# STM32L15x_Test.net
KiCad netlist of a schematic drawn in EAGLE
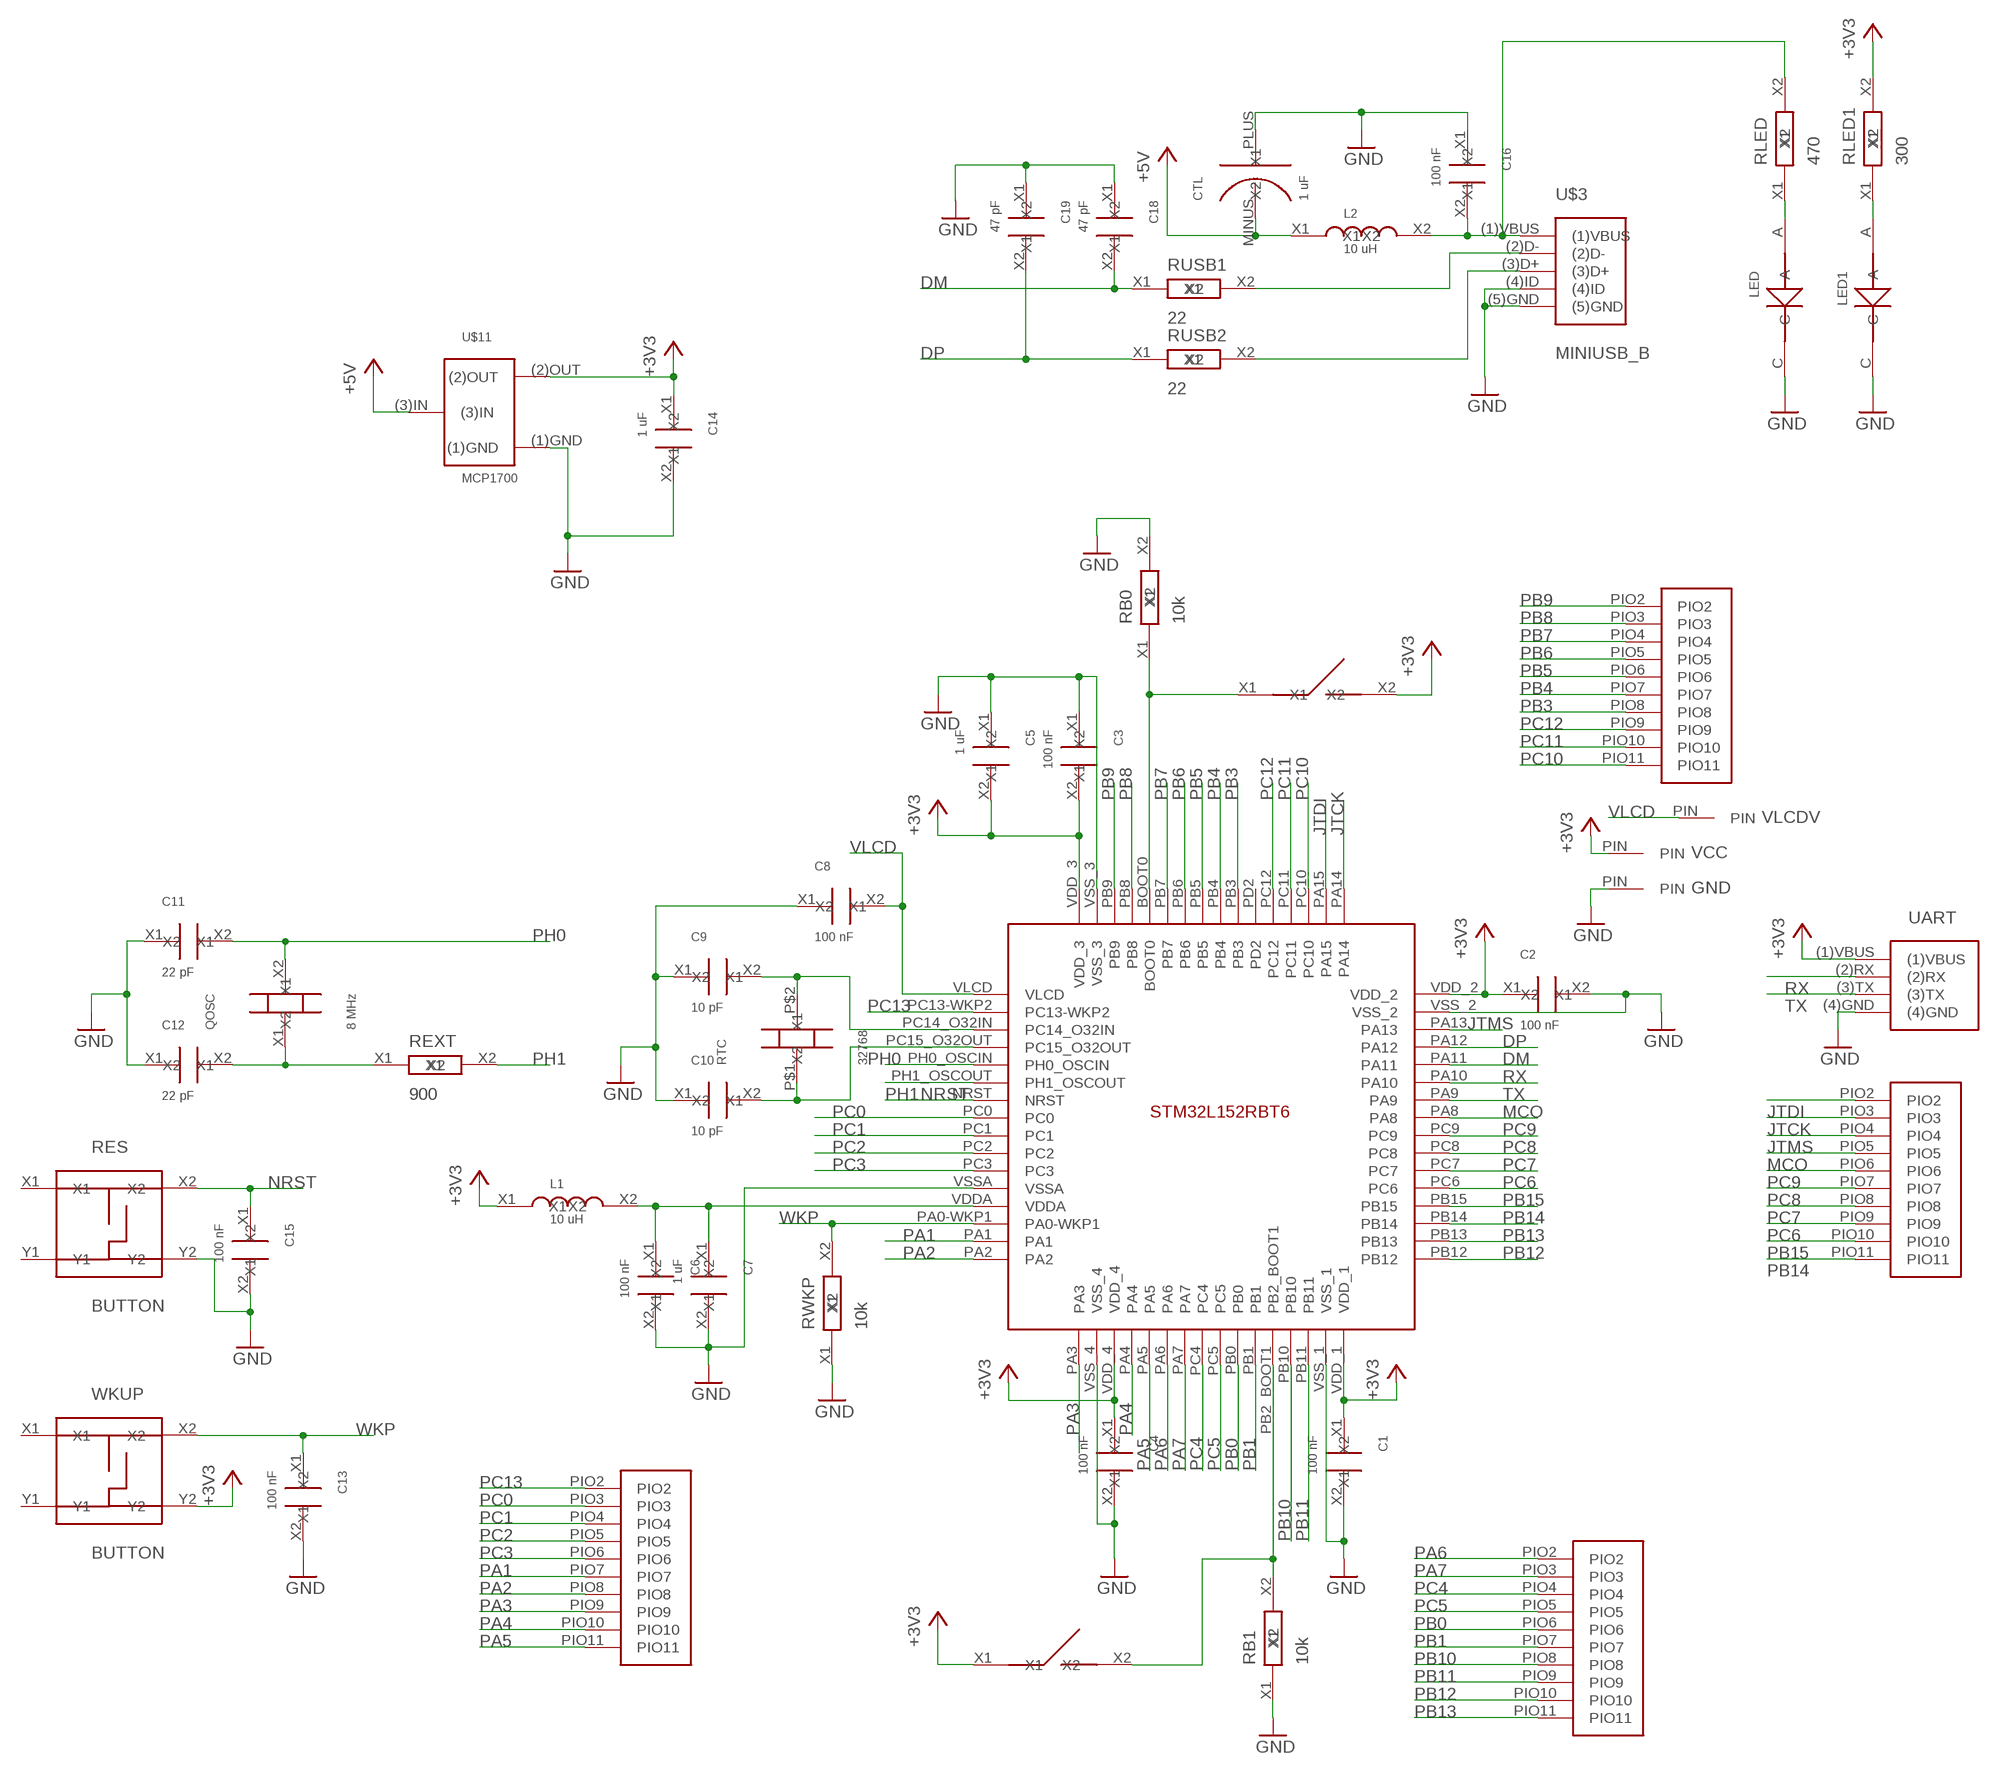
[diagram p0: schematic, sheet 1]

(export (version "E")
  (design (tool "Eeschema 10.0.6"))
  (components
    (comp (ref "C1")
      (value "100 nF")
      (footprint "eagle-import:SMD_2.1X1.25")
      (libsource (lib "eagle-import") (part "C_SMD_2.1X1.25"))
    )
    (comp (ref "C2")
      (value "100 nF")
      (footprint "eagle-import:SMD_2.1X1.25")
      (libsource (lib "eagle-import") (part "C_SMD_2.1X1.25"))
    )
    (comp (ref "C3")
      (value "100 nF")
      (footprint "eagle-import:SMD_2.1X1.25")
      (libsource (lib "eagle-import") (part "C_SMD_2.1X1.25"))
    )
    (comp (ref "C4")
      (value "100 nF")
      (footprint "eagle-import:SMD_2.1X1.25")
      (libsource (lib "eagle-import") (part "C_SMD_2.1X1.25"))
    )
    (comp (ref "C5")
      (value "1 uF")
      (footprint "eagle-import:SMD_2.1X1.25")
      (libsource (lib "eagle-import") (part "C_SMD_2.1X1.25"))
    )
    (comp (ref "C6")
      (value "100 nF")
      (footprint "eagle-import:SMD_2.1X1.25")
      (libsource (lib "eagle-import") (part "C_SMD_2.1X1.25"))
    )
    (comp (ref "C7")
      (value "1 uF")
      (footprint "eagle-import:SMD_2.1X1.25")
      (libsource (lib "eagle-import") (part "C_SMD_2.1X1.25"))
    )
    (comp (ref "C8")
      (value "100 nF")
      (footprint "eagle-import:SMD_2.1X1.25")
      (libsource (lib "eagle-import") (part "C_SMD_2.1X1.25"))
    )
    (comp (ref "C9")
      (value "10 pF")
      (footprint "eagle-import:SMD_2.1X1.25")
      (libsource (lib "eagle-import") (part "C_SMD_2.1X1.25"))
    )
    (comp (ref "C10")
      (value "10 pF")
      (footprint "eagle-import:SMD_2.1X1.25")
      (libsource (lib "eagle-import") (part "C_SMD_2.1X1.25"))
    )
    (comp (ref "C11")
      (value "22 pF")
      (footprint "eagle-import:SMD_2.1X1.25")
      (libsource (lib "eagle-import") (part "C_SMD_2.1X1.25"))
    )
    (comp (ref "C12")
      (value "22 pF")
      (footprint "eagle-import:SMD_2.1X1.25")
      (libsource (lib "eagle-import") (part "C_SMD_2.1X1.25"))
    )
    (comp (ref "C13")
      (value "100 nF")
      (footprint "eagle-import:SMD_2.1X1.25")
      (libsource (lib "eagle-import") (part "C_SMD_2.1X1.25"))
    )
    (comp (ref "C14")
      (value "1 uF")
      (footprint "eagle-import:SMD_2.1X1.25")
      (libsource (lib "eagle-import") (part "C_SMD_2.1X1.25"))
    )
    (comp (ref "C15")
      (value "100 nF")
      (footprint "eagle-import:SMD_2.1X1.25")
      (libsource (lib "eagle-import") (part "C_SMD_2.1X1.25"))
    )
    (comp (ref "C16")
      (value "100 nF")
      (footprint "eagle-import:SMD_2.1X1.25")
      (libsource (lib "eagle-import") (part "C_SMD_2.1X1.25"))
    )
    (comp (ref "C18")
      (value "47 pF")
      (footprint "eagle-import:SMD_2.1X1.25")
      (libsource (lib "eagle-import") (part "C_SMD_2.1X1.25"))
    )
    (comp (ref "C19")
      (value "47 pF")
      (footprint "eagle-import:SMD_2.1X1.25")
      (libsource (lib "eagle-import") (part "C_SMD_2.1X1.25"))
    )
    (comp (ref "CTL")
      (value "1 uF")
      (footprint "eagle-import:C_SMD_TA_A")
      (libsource (lib "eagle-import") (part "C_SMD_TA_A"))
    )
    (comp (ref "GND")
      (value "PIN")
      (footprint "eagle-import:PIN")
      (libsource (lib "eagle-import") (part "PIN"))
    )
    (comp (ref "L1")
      (value "10 uH")
      (footprint "eagle-import:SMD_2.1X1.25")
      (libsource (lib "eagle-import") (part "L_SMD_2.1X1.25"))
    )
    (comp (ref "L2")
      (value "10 uH")
      (footprint "eagle-import:SMD_2.1X1.25")
      (libsource (lib "eagle-import") (part "L_SMD_2.1X1.25"))
    )
    (comp (ref "LED")
      (value "LED0805")
      (footprint "eagle-import:SMD0805")
      (libsource (lib "eagle-import") (part "LED0805"))
    )
    (comp (ref "LED1")
      (value "LED0805")
      (footprint "eagle-import:SMD0805")
      (libsource (lib "eagle-import") (part "LED0805"))
    )
    (comp (ref "QOSC")
      (value "8 MHz")
      (footprint "eagle-import:QUARTZ_SMD")
      (libsource (lib "eagle-import") (part "QUARTZ_SMD"))
    )
    (comp (ref "RB0")
      (value "10k")
      (footprint "eagle-import:SMD_2.1X1.25")
      (libsource (lib "eagle-import") (part "R_SMD_2.1X1.25"))
    )
    (comp (ref "RB1")
      (value "10k")
      (footprint "eagle-import:SMD_2.1X1.25")
      (libsource (lib "eagle-import") (part "R_SMD_2.1X1.25"))
    )
    (comp (ref "RES")
      (value "BUTTON")
      (footprint "eagle-import:BUTTON")
      (libsource (lib "eagle-import") (part "BUTTON"))
    )
    (comp (ref "REXT")
      (value "900")
      (footprint "eagle-import:SMD_2.1X1.25")
      (libsource (lib "eagle-import") (part "R_SMD_2.1X1.25"))
    )
    (comp (ref "RLED")
      (value "470")
      (footprint "eagle-import:SMD_2.1X1.25")
      (libsource (lib "eagle-import") (part "R_SMD_2.1X1.25"))
    )
    (comp (ref "RLED1")
      (value "300")
      (footprint "eagle-import:SMD_2.1X1.25")
      (libsource (lib "eagle-import") (part "R_SMD_2.1X1.25"))
    )
    (comp (ref "RTC")
      (value "32768")
      (footprint "eagle-import:QUARTZ_CYL")
      (libsource (lib "eagle-import") (part "QUARTZ_CYL"))
    )
    (comp (ref "RUSB1")
      (value "22")
      (footprint "eagle-import:SMD_2.1X1.25")
      (libsource (lib "eagle-import") (part "R_SMD_2.1X1.25"))
    )
    (comp (ref "RUSB2")
      (value "22")
      (footprint "eagle-import:SMD_2.1X1.25")
      (libsource (lib "eagle-import") (part "R_SMD_2.1X1.25"))
    )
    (comp (ref "RWKP")
      (value "10k")
      (footprint "eagle-import:SMD_2.1X1.25")
      (libsource (lib "eagle-import") (part "R_SMD_2.1X1.25"))
    )
    (comp (ref "U$1")
      (value "STM32L15XRBT6")
      (footprint "eagle-import:STM32L152RBT6")
      (libsource (lib "eagle-import") (part "STM32L15XRBT6"))
    )
    (comp (ref "U$2")
      (value "PIO_10")
      (footprint "eagle-import:PIO_10")
      (libsource (lib "eagle-import") (part "PIO_10"))
    )
    (comp (ref "U$3")
      (value "MINIUSB_B")
      (footprint "eagle-import:MINIUSB_B")
      (libsource (lib "eagle-import") (part "MINIUSB_B"))
    )
    (comp (ref "U$5")
      (value "PIO_10")
      (footprint "eagle-import:PIO_10")
      (libsource (lib "eagle-import") (part "PIO_10"))
    )
    (comp (ref "U$6")
      (value "PIO_10")
      (footprint "eagle-import:PIO_10")
      (libsource (lib "eagle-import") (part "PIO_10"))
    )
    (comp (ref "U$7")
      (value "PIO_10")
      (footprint "eagle-import:PIO_10")
      (libsource (lib "eagle-import") (part "PIO_10"))
    )
    (comp (ref "U$8")
      (value "DIP_1")
      (footprint "eagle-import:DIP_1")
      (libsource (lib "eagle-import") (part "DIP_1"))
    )
    (comp (ref "U$9")
      (value "DIP_1")
      (footprint "eagle-import:DIP_1")
      (libsource (lib "eagle-import") (part "DIP_1"))
    )
    (comp (ref "U$11")
      (value "MCP1700")
      (footprint "eagle-import:MCP1700")
      (libsource (lib "eagle-import") (part "MCP1700"))
    )
    (comp (ref "UART")
      (value "USART")
      (footprint "eagle-import:USART")
      (libsource (lib "eagle-import") (part "USART"))
    )
    (comp (ref "VCC")
      (value "PIN")
      (footprint "eagle-import:PIN")
      (libsource (lib "eagle-import") (part "PIN"))
    )
    (comp (ref "VLCDV")
      (value "PIN")
      (footprint "eagle-import:PIN")
      (libsource (lib "eagle-import") (part "PIN"))
    )
    (comp (ref "WKUP")
      (value "BUTTON")
      (footprint "eagle-import:BUTTON")
      (libsource (lib "eagle-import") (part "BUTTON"))
    )
  )
  (nets
    (net (code "1") (name "+3V3") (class "Default")
      (node (ref "C1") (pin "X1") (pinfunction "X1_X1") (pintype "bidirectional"))
      (node (ref "C14") (pin "X1") (pinfunction "X1_X1") (pintype "bidirectional"))
      (node (ref "C2") (pin "X1") (pinfunction "X1_X1") (pintype "bidirectional"))
      (node (ref "C3") (pin "X2") (pinfunction "X2_X2") (pintype "bidirectional"))
      (node (ref "C4") (pin "X1") (pinfunction "X1_X1") (pintype "bidirectional"))
      (node (ref "C5") (pin "X2") (pinfunction "X2_X2") (pintype "bidirectional"))
      (node (ref "L1") (pin "X1") (pinfunction "X1_X1") (pintype "bidirectional"))
      (node (ref "RLED1") (pin "X2") (pinfunction "X2_X2") (pintype "bidirectional"))
      (node (ref "U$1") (pin "VDD_1") (pinfunction "VDD_1_VDD_1") (pintype "bidirectional"))
      (node (ref "U$1") (pin "VDD_2") (pinfunction "VDD_2_VDD_2") (pintype "bidirectional"))
      (node (ref "U$1") (pin "VDD_3") (pinfunction "VDD_3_VDD_3") (pintype "bidirectional"))
      (node (ref "U$1") (pin "VDD_4") (pinfunction "VDD_4_VDD_4") (pintype "bidirectional"))
      (node (ref "U$11") (pin "(2)OUT") (pinfunction "(2)OUT_(2)OUT") (pintype "bidirectional"))
      (node (ref "U$8") (pin "X2") (pinfunction "X2_X2") (pintype "bidirectional"))
      (node (ref "U$9") (pin "X1") (pinfunction "X1_X1") (pintype "bidirectional"))
      (node (ref "UART") (pin "(1)VBUS") (pinfunction "(1)VBUS_(1)VBUS") (pintype "bidirectional"))
      (node (ref "VCC") (pin "PIN") (pinfunction "PIN_PIN") (pintype "bidirectional"))
      (node (ref "WKUP") (pin "Y2") (pinfunction "Y2_Y2") (pintype "bidirectional"))
    )
    (net (code "2") (name "+5V") (class "Default")
      (node (ref "CTL") (pin "MINUS") (pinfunction "X1_MINUS") (pintype "bidirectional"))
      (node (ref "L2") (pin "X1") (pinfunction "X1_X1") (pintype "bidirectional"))
      (node (ref "U$11") (pin "(3)IN") (pinfunction "(3)IN_(3)IN") (pintype "bidirectional"))
    )
    (net (code "3") (name "/DM") (class "Default")
      (node (ref "C18") (pin "X2") (pinfunction "X2_X2") (pintype "bidirectional"))
      (node (ref "RUSB1") (pin "X1") (pinfunction "X1_X1") (pintype "bidirectional"))
      (node (ref "U$1") (pin "PA11") (pinfunction "PA11_PA11") (pintype "bidirectional"))
    )
    (net (code "4") (name "/DP") (class "Default")
      (node (ref "C19") (pin "X2") (pinfunction "X2_X2") (pintype "bidirectional"))
      (node (ref "RUSB2") (pin "X1") (pinfunction "X1_X1") (pintype "bidirectional"))
      (node (ref "U$1") (pin "PA12") (pinfunction "PA12_PA12") (pintype "bidirectional"))
    )
    (net (code "5") (name "/JTCK") (class "Default")
      (node (ref "U$1") (pin "PA14") (pinfunction "PA14_PA14") (pintype "bidirectional"))
      (node (ref "U$6") (pin "PIO3") (pinfunction "PIO3_PIO3") (pintype "bidirectional"))
    )
    (net (code "6") (name "/JTDI") (class "Default")
      (node (ref "U$1") (pin "PA15") (pinfunction "PA15_PA15") (pintype "bidirectional"))
      (node (ref "U$6") (pin "PIO2") (pinfunction "PIO2_PIO2") (pintype "bidirectional"))
    )
    (net (code "7") (name "/JTMS") (class "Default")
      (node (ref "U$1") (pin "PA13") (pinfunction "PA13_PA13") (pintype "bidirectional"))
      (node (ref "U$6") (pin "PIO4") (pinfunction "PIO4_PIO4") (pintype "bidirectional"))
    )
    (net (code "8") (name "/MCO") (class "Default")
      (node (ref "U$1") (pin "PA8") (pinfunction "PA8_PA8") (pintype "bidirectional"))
      (node (ref "U$6") (pin "PIO5") (pinfunction "PIO5_PIO5") (pintype "bidirectional"))
    )
    (net (code "9") (name "/NRST") (class "Default")
      (node (ref "C15") (pin "X1") (pinfunction "X1_X1") (pintype "bidirectional"))
      (node (ref "RES") (pin "X2") (pinfunction "X2_X2") (pintype "bidirectional"))
      (node (ref "U$1") (pin "NRST") (pinfunction "NRST_NRST") (pintype "bidirectional"))
    )
    (net (code "10") (name "/PA1") (class "Default")
      (node (ref "U$1") (pin "PA1") (pinfunction "PA1_PA1") (pintype "bidirectional"))
      (node (ref "U$2") (pin "PIO7") (pinfunction "PIO7_PIO7") (pintype "bidirectional"))
    )
    (net (code "11") (name "/PA2") (class "Default")
      (node (ref "U$1") (pin "PA2") (pinfunction "PA2_PA2") (pintype "bidirectional"))
      (node (ref "U$2") (pin "PIO8") (pinfunction "PIO8_PIO8") (pintype "bidirectional"))
    )
    (net (code "12") (name "/PA3") (class "Default")
      (node (ref "U$1") (pin "PA3") (pinfunction "PA3_PA3") (pintype "bidirectional"))
      (node (ref "U$2") (pin "PIO9") (pinfunction "PIO9_PIO9") (pintype "bidirectional"))
    )
    (net (code "13") (name "/PA4") (class "Default")
      (node (ref "U$1") (pin "PA4") (pinfunction "PA4_PA4") (pintype "bidirectional"))
      (node (ref "U$2") (pin "PIO10") (pinfunction "PIO10_PIO10") (pintype "bidirectional"))
    )
    (net (code "14") (name "/PA5") (class "Default")
      (node (ref "U$1") (pin "PA5") (pinfunction "PA5_PA5") (pintype "bidirectional"))
      (node (ref "U$2") (pin "PIO11") (pinfunction "PIO11_PIO11") (pintype "bidirectional"))
    )
    (net (code "15") (name "/PA6") (class "Default")
      (node (ref "U$1") (pin "PA6") (pinfunction "PA6_PA6") (pintype "bidirectional"))
      (node (ref "U$5") (pin "PIO2") (pinfunction "PIO2_PIO2") (pintype "bidirectional"))
    )
    (net (code "16") (name "/PA7") (class "Default")
      (node (ref "U$1") (pin "PA7") (pinfunction "PA7_PA7") (pintype "bidirectional"))
      (node (ref "U$5") (pin "PIO3") (pinfunction "PIO3_PIO3") (pintype "bidirectional"))
    )
    (net (code "17") (name "/PB0") (class "Default")
      (node (ref "U$1") (pin "PB0") (pinfunction "PB0_PB0") (pintype "bidirectional"))
      (node (ref "U$5") (pin "PIO6") (pinfunction "PIO6_PIO6") (pintype "bidirectional"))
    )
    (net (code "18") (name "/PB1") (class "Default")
      (node (ref "U$1") (pin "PB1") (pinfunction "PB1_PB1") (pintype "bidirectional"))
      (node (ref "U$5") (pin "PIO7") (pinfunction "PIO7_PIO7") (pintype "bidirectional"))
    )
    (net (code "19") (name "/PB3") (class "Default")
      (node (ref "U$1") (pin "PB3") (pinfunction "PB3_PB3") (pintype "bidirectional"))
      (node (ref "U$7") (pin "PIO8") (pinfunction "PIO8_PIO8") (pintype "bidirectional"))
    )
    (net (code "20") (name "/PB4") (class "Default")
      (node (ref "U$1") (pin "PB4") (pinfunction "PB4_PB4") (pintype "bidirectional"))
      (node (ref "U$7") (pin "PIO7") (pinfunction "PIO7_PIO7") (pintype "bidirectional"))
    )
    (net (code "21") (name "/PB5") (class "Default")
      (node (ref "U$1") (pin "PB5") (pinfunction "PB5_PB5") (pintype "bidirectional"))
      (node (ref "U$7") (pin "PIO6") (pinfunction "PIO6_PIO6") (pintype "bidirectional"))
    )
    (net (code "22") (name "/PB6") (class "Default")
      (node (ref "U$1") (pin "PB6") (pinfunction "PB6_PB6") (pintype "bidirectional"))
      (node (ref "U$7") (pin "PIO5") (pinfunction "PIO5_PIO5") (pintype "bidirectional"))
    )
    (net (code "23") (name "/PB7") (class "Default")
      (node (ref "U$1") (pin "PB7") (pinfunction "PB7_PB7") (pintype "bidirectional"))
      (node (ref "U$7") (pin "PIO4") (pinfunction "PIO4_PIO4") (pintype "bidirectional"))
    )
    (net (code "24") (name "/PB8") (class "Default")
      (node (ref "U$1") (pin "PB8") (pinfunction "PB8_PB8") (pintype "bidirectional"))
      (node (ref "U$7") (pin "PIO3") (pinfunction "PIO3_PIO3") (pintype "bidirectional"))
    )
    (net (code "25") (name "/PB9") (class "Default")
      (node (ref "U$1") (pin "PB9") (pinfunction "PB9_PB9") (pintype "bidirectional"))
      (node (ref "U$7") (pin "PIO2") (pinfunction "PIO2_PIO2") (pintype "bidirectional"))
    )
    (net (code "26") (name "/PB10") (class "Default")
      (node (ref "U$1") (pin "PB10") (pinfunction "PB10_PB10") (pintype "bidirectional"))
      (node (ref "U$5") (pin "PIO8") (pinfunction "PIO8_PIO8") (pintype "bidirectional"))
    )
    (net (code "27") (name "/PB11") (class "Default")
      (node (ref "U$1") (pin "PB11") (pinfunction "PB11_PB11") (pintype "bidirectional"))
      (node (ref "U$5") (pin "PIO9") (pinfunction "PIO9_PIO9") (pintype "bidirectional"))
    )
    (net (code "28") (name "/PB12") (class "Default")
      (node (ref "U$1") (pin "PB12") (pinfunction "PB12_PB12") (pintype "bidirectional"))
      (node (ref "U$5") (pin "PIO10") (pinfunction "PIO10_PIO10") (pintype "bidirectional"))
    )
    (net (code "29") (name "/PB13") (class "Default")
      (node (ref "U$1") (pin "PB13") (pinfunction "PB13_PB13") (pintype "bidirectional"))
      (node (ref "U$5") (pin "PIO11") (pinfunction "PIO11_PIO11") (pintype "bidirectional"))
    )
    (net (code "30") (name "/PB14") (class "Default")
      (node (ref "U$1") (pin "PB14") (pinfunction "PB14_PB14") (pintype "bidirectional"))
      (node (ref "U$6") (pin "PIO11") (pinfunction "PIO11_PIO11") (pintype "bidirectional"))
    )
    (net (code "31") (name "/PB15") (class "Default")
      (node (ref "U$1") (pin "PB15") (pinfunction "PB15_PB15") (pintype "bidirectional"))
      (node (ref "U$6") (pin "PIO10") (pinfunction "PIO10_PIO10") (pintype "bidirectional"))
    )
    (net (code "32") (name "/PC0") (class "Default")
      (node (ref "U$1") (pin "PC0") (pinfunction "PC0_PC0") (pintype "bidirectional"))
      (node (ref "U$2") (pin "PIO3") (pinfunction "PIO3_PIO3") (pintype "bidirectional"))
    )
    (net (code "33") (name "/PC1") (class "Default")
      (node (ref "U$1") (pin "PC1") (pinfunction "PC1_PC1") (pintype "bidirectional"))
      (node (ref "U$2") (pin "PIO4") (pinfunction "PIO4_PIO4") (pintype "bidirectional"))
    )
    (net (code "34") (name "/PC2") (class "Default")
      (node (ref "U$1") (pin "PC2") (pinfunction "PC2_PC2") (pintype "bidirectional"))
      (node (ref "U$2") (pin "PIO5") (pinfunction "PIO5_PIO5") (pintype "bidirectional"))
    )
    (net (code "35") (name "/PC3") (class "Default")
      (node (ref "U$1") (pin "PC3") (pinfunction "PC3_PC3") (pintype "bidirectional"))
      (node (ref "U$2") (pin "PIO6") (pinfunction "PIO6_PIO6") (pintype "bidirectional"))
    )
    (net (code "36") (name "/PC4") (class "Default")
      (node (ref "U$1") (pin "PC4") (pinfunction "PC4_PC4") (pintype "bidirectional"))
      (node (ref "U$5") (pin "PIO4") (pinfunction "PIO4_PIO4") (pintype "bidirectional"))
    )
    (net (code "37") (name "/PC5") (class "Default")
      (node (ref "U$1") (pin "PC5") (pinfunction "PC5_PC5") (pintype "bidirectional"))
      (node (ref "U$5") (pin "PIO5") (pinfunction "PIO5_PIO5") (pintype "bidirectional"))
    )
    (net (code "38") (name "/PC6") (class "Default")
      (node (ref "U$1") (pin "PC6") (pinfunction "PC6_PC6") (pintype "bidirectional"))
      (node (ref "U$6") (pin "PIO9") (pinfunction "PIO9_PIO9") (pintype "bidirectional"))
    )
    (net (code "39") (name "/PC7") (class "Default")
      (node (ref "U$1") (pin "PC7") (pinfunction "PC7_PC7") (pintype "bidirectional"))
      (node (ref "U$6") (pin "PIO8") (pinfunction "PIO8_PIO8") (pintype "bidirectional"))
    )
    (net (code "40") (name "/PC8") (class "Default")
      (node (ref "U$1") (pin "PC8") (pinfunction "PC8_PC8") (pintype "bidirectional"))
      (node (ref "U$6") (pin "PIO7") (pinfunction "PIO7_PIO7") (pintype "bidirectional"))
    )
    (net (code "41") (name "/PC9") (class "Default")
      (node (ref "U$1") (pin "PC9") (pinfunction "PC9_PC9") (pintype "bidirectional"))
      (node (ref "U$6") (pin "PIO6") (pinfunction "PIO6_PIO6") (pintype "bidirectional"))
    )
    (net (code "42") (name "/PC10") (class "Default")
      (node (ref "U$1") (pin "PC10") (pinfunction "PC10_PC10") (pintype "bidirectional"))
      (node (ref "U$7") (pin "PIO11") (pinfunction "PIO11_PIO11") (pintype "bidirectional"))
    )
    (net (code "43") (name "/PC11") (class "Default")
      (node (ref "U$1") (pin "PC11") (pinfunction "PC11_PC11") (pintype "bidirectional"))
      (node (ref "U$7") (pin "PIO10") (pinfunction "PIO10_PIO10") (pintype "bidirectional"))
    )
    (net (code "44") (name "/PC12") (class "Default")
      (node (ref "U$1") (pin "PC12") (pinfunction "PC12_PC12") (pintype "bidirectional"))
      (node (ref "U$7") (pin "PIO9") (pinfunction "PIO9_PIO9") (pintype "bidirectional"))
    )
    (net (code "45") (name "/PC13") (class "Default")
      (node (ref "U$1") (pin "PC13-WKP2") (pinfunction "PC13-WKP2_PC13-WKP2") (pintype "bidirectional"))
      (node (ref "U$2") (pin "PIO2") (pinfunction "PIO2_PIO2") (pintype "bidirectional"))
    )
    (net (code "46") (name "/PH0") (class "Default")
      (node (ref "C11") (pin "X2") (pinfunction "X2_X2") (pintype "bidirectional"))
      (node (ref "QOSC") (pin "X2") (pinfunction "X2_X2") (pintype "bidirectional"))
      (node (ref "U$1") (pin "PH0_OSCIN") (pinfunction "PH0_OSCIN_PH0_OSCIN") (pintype "bidirectional"))
    )
    (net (code "47") (name "/PH1") (class "Default")
      (node (ref "REXT") (pin "X2") (pinfunction "X2_X2") (pintype "bidirectional"))
      (node (ref "U$1") (pin "PH1_OSCOUT") (pinfunction "PH1_OSCOUT_PH1_OSCOUT") (pintype "bidirectional"))
    )
    (net (code "48") (name "/RX") (class "Default")
      (node (ref "U$1") (pin "PA10") (pinfunction "PA10_PA10") (pintype "bidirectional"))
      (node (ref "UART") (pin "(2)RX") (pinfunction "(2)RX_(2)RX") (pintype "bidirectional"))
    )
    (net (code "49") (name "/TX") (class "Default")
      (node (ref "U$1") (pin "PA9") (pinfunction "PA9_PA9") (pintype "bidirectional"))
      (node (ref "UART") (pin "(3)TX") (pinfunction "(3)TX_(3)TX") (pintype "bidirectional"))
    )
    (net (code "50") (name "/VLCD") (class "Default")
      (node (ref "C8") (pin "X2") (pinfunction "X2_X2") (pintype "bidirectional"))
      (node (ref "U$1") (pin "VLCD") (pinfunction "VLCD_VLCD") (pintype "bidirectional"))
      (node (ref "VLCDV") (pin "PIN") (pinfunction "PIN_PIN") (pintype "bidirectional"))
    )
    (net (code "51") (name "/WKP") (class "Default")
      (node (ref "C13") (pin "X1") (pinfunction "X1_X1") (pintype "bidirectional"))
      (node (ref "RWKP") (pin "X2") (pinfunction "X2_X2") (pintype "bidirectional"))
      (node (ref "U$1") (pin "PA0-WKP1") (pinfunction "PA0-WKP1_PA0-WKP1") (pintype "bidirectional"))
      (node (ref "WKUP") (pin "X2") (pinfunction "X2_X2") (pintype "bidirectional"))
    )
    (net (code "52") (name "GND") (class "Default")
      (node (ref "C1") (pin "X2") (pinfunction "X2_X2") (pintype "bidirectional"))
      (node (ref "C10") (pin "X1") (pinfunction "X1_X1") (pintype "bidirectional"))
      (node (ref "C11") (pin "X1") (pinfunction "X1_X1") (pintype "bidirectional"))
      (node (ref "C12") (pin "X1") (pinfunction "X1_X1") (pintype "bidirectional"))
      (node (ref "C13") (pin "X2") (pinfunction "X2_X2") (pintype "bidirectional"))
      (node (ref "C14") (pin "X2") (pinfunction "X2_X2") (pintype "bidirectional"))
      (node (ref "C15") (pin "X2") (pinfunction "X2_X2") (pintype "bidirectional"))
      (node (ref "C16") (pin "X1") (pinfunction "X1_X1") (pintype "bidirectional"))
      (node (ref "C18") (pin "X1") (pinfunction "X1_X1") (pintype "bidirectional"))
      (node (ref "C19") (pin "X1") (pinfunction "X1_X1") (pintype "bidirectional"))
      (node (ref "C2") (pin "X2") (pinfunction "X2_X2") (pintype "bidirectional"))
      (node (ref "C3") (pin "X1") (pinfunction "X1_X1") (pintype "bidirectional"))
      (node (ref "C4") (pin "X2") (pinfunction "X2_X2") (pintype "bidirectional"))
      (node (ref "C5") (pin "X1") (pinfunction "X1_X1") (pintype "bidirectional"))
      (node (ref "C6") (pin "X2") (pinfunction "X2_X2") (pintype "bidirectional"))
      (node (ref "C7") (pin "X2") (pinfunction "X2_X2") (pintype "bidirectional"))
      (node (ref "C8") (pin "X1") (pinfunction "X1_X1") (pintype "bidirectional"))
      (node (ref "C9") (pin "X1") (pinfunction "X1_X1") (pintype "bidirectional"))
      (node (ref "CTL") (pin "PLUS") (pinfunction "X2_PLUS") (pintype "bidirectional"))
      (node (ref "GND") (pin "PIN") (pinfunction "PIN_PIN") (pintype "bidirectional"))
      (node (ref "LED") (pin "C") (pinfunction "C_C") (pintype "bidirectional"))
      (node (ref "LED1") (pin "C") (pinfunction "C_C") (pintype "bidirectional"))
      (node (ref "RB0") (pin "X2") (pinfunction "X2_X2") (pintype "bidirectional"))
      (node (ref "RB1") (pin "X1") (pinfunction "X1_X1") (pintype "bidirectional"))
      (node (ref "RES") (pin "Y2") (pinfunction "Y2_Y2") (pintype "bidirectional"))
      (node (ref "RWKP") (pin "X1") (pinfunction "X1_X1") (pintype "bidirectional"))
      (node (ref "U$1") (pin "VSSA") (pinfunction "VSSA_VSSA") (pintype "bidirectional"))
      (node (ref "U$1") (pin "VSS_1") (pinfunction "VSS_1_VSS_1") (pintype "bidirectional"))
      (node (ref "U$1") (pin "VSS_2") (pinfunction "VSS_2_VSS_2") (pintype "bidirectional"))
      (node (ref "U$1") (pin "VSS_3") (pinfunction "VSS_3_VSS_3") (pintype "bidirectional"))
      (node (ref "U$1") (pin "VSS_4") (pinfunction "VSS_4_VSS_4") (pintype "bidirectional"))
      (node (ref "U$11") (pin "(1)GND") (pinfunction "(1)GND_(1)GND") (pintype "bidirectional"))
      (node (ref "U$3") (pin "(4)ID") (pinfunction "(4)ID_(4)ID") (pintype "bidirectional"))
      (node (ref "U$3") (pin "(5)GND") (pinfunction "(5)GND_(5)GND") (pintype "bidirectional"))
      (node (ref "UART") (pin "(4)GND") (pinfunction "(4)GND_(4)GND") (pintype "bidirectional"))
    )
    (net (code "53") (name "Net-(C6-PadX1)") (class "Default")
      (node (ref "C6") (pin "X1") (pinfunction "X1_X1") (pintype "bidirectional"))
      (node (ref "C7") (pin "X1") (pinfunction "X1_X1") (pintype "bidirectional"))
      (node (ref "L1") (pin "X2") (pinfunction "X2_X2") (pintype "bidirectional"))
      (node (ref "U$1") (pin "VDDA") (pinfunction "VDDA_VDDA") (pintype "bidirectional"))
    )
    (net (code "54") (name "Net-(C12-PadX2)") (class "Default")
      (node (ref "C12") (pin "X2") (pinfunction "X2_X2") (pintype "bidirectional"))
      (node (ref "QOSC") (pin "X1") (pinfunction "X1_X1") (pintype "bidirectional"))
      (node (ref "REXT") (pin "X1") (pinfunction "X1_X1") (pintype "bidirectional"))
    )
    (net (code "55") (name "Net-(C16-PadX2)") (class "Default")
      (node (ref "C16") (pin "X2") (pinfunction "X2_X2") (pintype "bidirectional"))
      (node (ref "L2") (pin "X2") (pinfunction "X2_X2") (pintype "bidirectional"))
      (node (ref "RLED") (pin "X2") (pinfunction "X2_X2") (pintype "bidirectional"))
      (node (ref "U$3") (pin "(1)VBUS") (pinfunction "(1)VBUS_(1)VBUS") (pintype "bidirectional"))
    )
    (net (code "56") (name "Net-(LED-PadA)") (class "Default")
      (node (ref "LED") (pin "A") (pinfunction "A_A") (pintype "bidirectional"))
      (node (ref "RLED") (pin "X1") (pinfunction "X1_X1") (pintype "bidirectional"))
    )
    (net (code "57") (name "Net-(LED1-PadA)") (class "Default")
      (node (ref "LED1") (pin "A") (pinfunction "A_A") (pintype "bidirectional"))
      (node (ref "RLED1") (pin "X1") (pinfunction "X1_X1") (pintype "bidirectional"))
    )
    (net (code "58") (name "Net-(RB0-PadX1)") (class "Default")
      (node (ref "RB0") (pin "X1") (pinfunction "X1_X1") (pintype "bidirectional"))
      (node (ref "U$1") (pin "BOOT0") (pinfunction "BOOT0_BOOT0") (pintype "bidirectional"))
      (node (ref "U$8") (pin "X1") (pinfunction "X1_X1") (pintype "bidirectional"))
    )
    (net (code "59") (name "Net-(RB1-PadX2)") (class "Default")
      (node (ref "RB1") (pin "X2") (pinfunction "X2_X2") (pintype "bidirectional"))
      (node (ref "U$1") (pin "PB2_BOOT1") (pinfunction "PB2_BOOT1_PB2_BOOT1") (pintype "bidirectional"))
      (node (ref "U$9") (pin "X2") (pinfunction "X2_X2") (pintype "bidirectional"))
    )
    (net (code "60") (name "Net-(RTC-X1)") (class "Default")
      (node (ref "C10") (pin "X2") (pinfunction "X2_X2") (pintype "bidirectional"))
      (node (ref "RTC") (pin "P$1") (pinfunction "X1_P$1") (pintype "bidirectional"))
      (node (ref "U$1") (pin "PC15_O32OUT") (pinfunction "PC15_O32OUT_PC15_O32OUT") (pintype "bidirectional"))
    )
    (net (code "61") (name "Net-(RTC-X2)") (class "Default")
      (node (ref "C9") (pin "X2") (pinfunction "X2_X2") (pintype "bidirectional"))
      (node (ref "RTC") (pin "P$2") (pinfunction "X2_P$2") (pintype "bidirectional"))
      (node (ref "U$1") (pin "PC14_O32IN") (pinfunction "PC14_O32IN_PC14_O32IN") (pintype "bidirectional"))
    )
    (net (code "62") (name "Net-(RUSB1-PadX2)") (class "Default")
      (node (ref "RUSB1") (pin "X2") (pinfunction "X2_X2") (pintype "bidirectional"))
      (node (ref "U$3") (pin "(2)D-") (pinfunction "(2)D-_(2)D-") (pintype "bidirectional"))
    )
    (net (code "63") (name "Net-(RUSB2-PadX2)") (class "Default")
      (node (ref "RUSB2") (pin "X2") (pinfunction "X2_X2") (pintype "bidirectional"))
      (node (ref "U$3") (pin "(3)D+") (pinfunction "(3)D+_(3)D+") (pintype "bidirectional"))
    )
    (net (code "64") (name "unconnected-(RES-PadX1)") (class "Default")
      (node (ref "RES") (pin "X1") (pinfunction "X1_X1") (pintype "bidirectional"))
    )
    (net (code "65") (name "unconnected-(RES-PadY1)") (class "Default")
      (node (ref "RES") (pin "Y1") (pinfunction "Y1_Y1") (pintype "bidirectional"))
    )
    (net (code "66") (name "unconnected-(U$1-PadPD2)") (class "Default")
      (node (ref "U$1") (pin "PD2") (pinfunction "PD2_PD2") (pintype "bidirectional"))
    )
    (net (code "67") (name "unconnected-(WKUP-PadX1)") (class "Default")
      (node (ref "WKUP") (pin "X1") (pinfunction "X1_X1") (pintype "bidirectional"))
    )
    (net (code "68") (name "unconnected-(WKUP-PadY1)") (class "Default")
      (node (ref "WKUP") (pin "Y1") (pinfunction "Y1_Y1") (pintype "bidirectional"))
    )
  )
)
